# WKMiniFlyG4.net
KiCad netlist of a schematic drawn in EasyEDA Pro
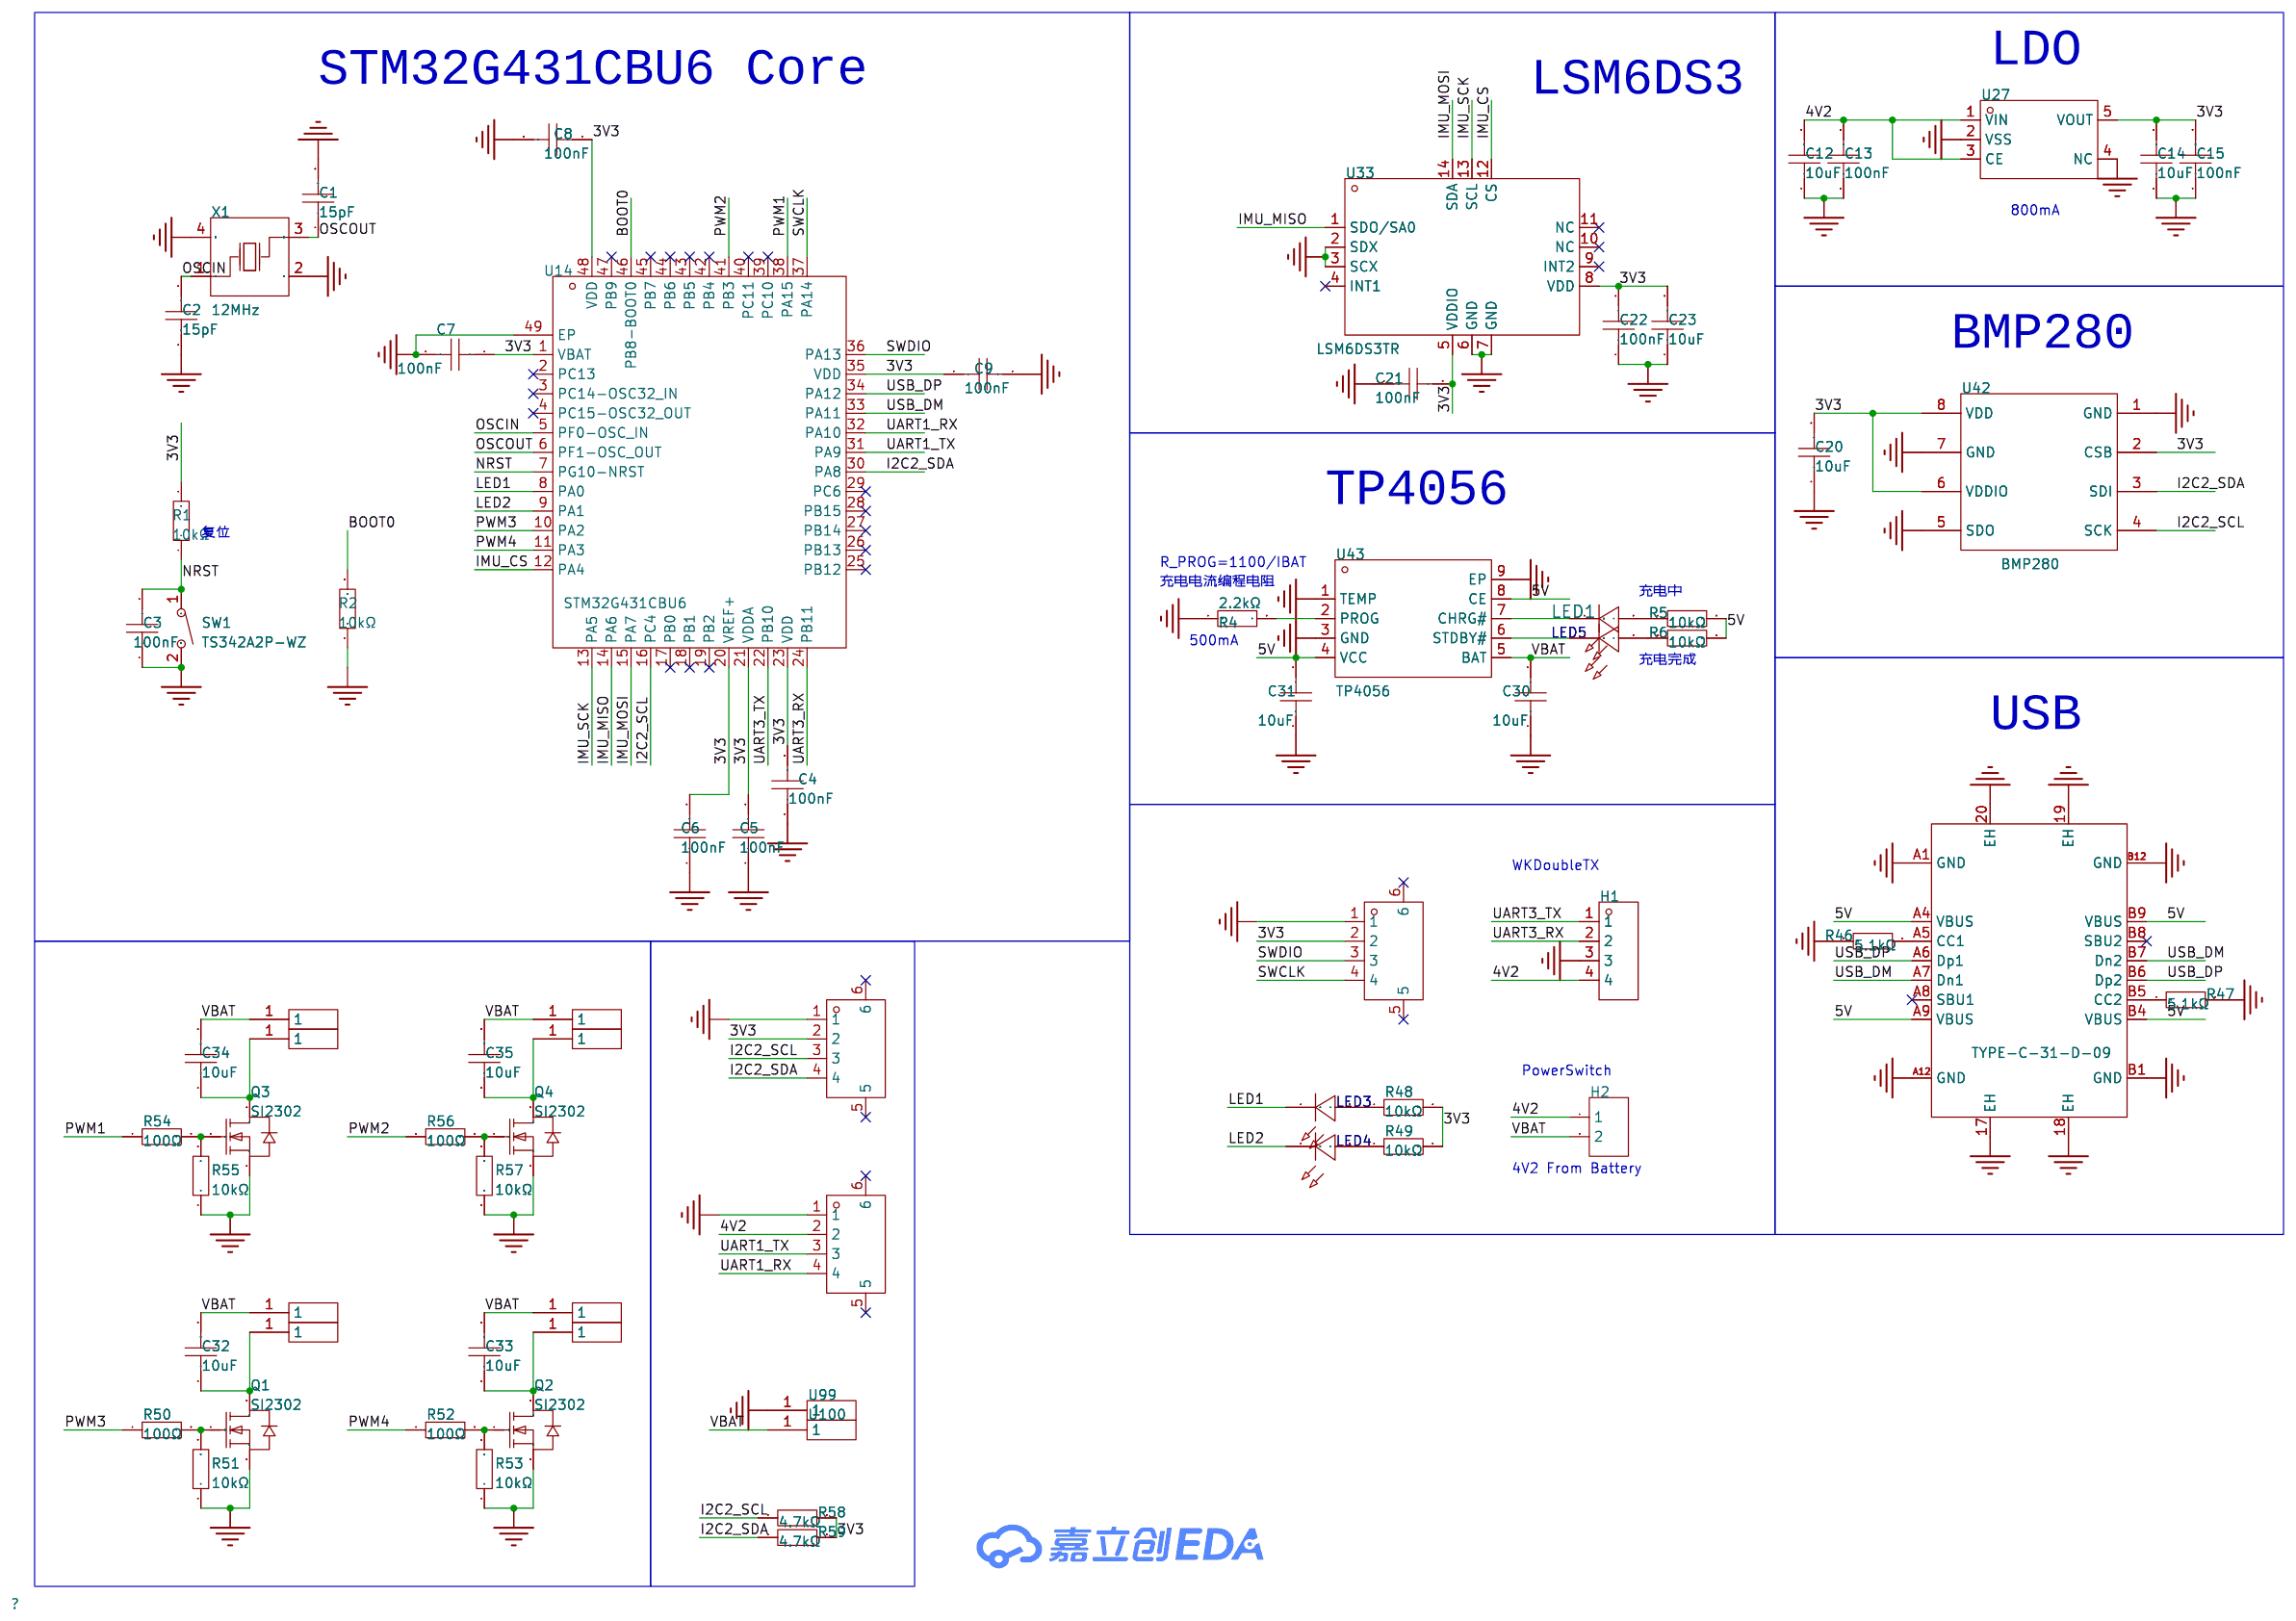
[diagram p0: schematic sheet]

(export (version "E")
  (design (tool "Eeschema 10.0.6"))
  (components
    (comp (ref "C1")
      (value "15pF")
      (footprint "easyedapro:C0603")
      (fields
        (field (name "Manufacturer Part") "CL10C150JB8NNNC")
        (field (name "Manufacturer") "SAMSUNG(三星)")
      )
      (libsource (lib "easyedapro") (part "CapAcitance"))
    )
    (comp (ref "C2")
      (value "15pF")
      (footprint "easyedapro:C0603")
      (fields
        (field (name "Manufacturer Part") "CL10C150JB8NNNC")
        (field (name "Manufacturer") "SAMSUNG(三星)")
      )
      (libsource (lib "easyedapro") (part "CapAcitance"))
    )
    (comp (ref "C3")
      (value "100nF")
      (footprint "easyedapro:C0603")
      (fields
        (field (name "Manufacturer Part") "CC0603KRX7R9BB104")
        (field (name "Manufacturer") "YAGEO(国巨)")
      )
      (libsource (lib "easyedapro") (part "CapAcitance"))
    )
    (comp (ref "C4")
      (value "100nF")
      (footprint "easyedapro:C0603")
      (fields
        (field (name "Manufacturer Part") "CC0603KRX7R9BB104")
        (field (name "Manufacturer") "YAGEO(国巨)")
      )
      (libsource (lib "easyedapro") (part "CapAcitance"))
    )
    (comp (ref "C5")
      (value "100nF")
      (footprint "easyedapro:C0603")
      (fields
        (field (name "Manufacturer Part") "CC0603KRX7R9BB104")
        (field (name "Manufacturer") "YAGEO(国巨)")
      )
      (libsource (lib "easyedapro") (part "CapAcitance"))
    )
    (comp (ref "C6")
      (value "100nF")
      (footprint "easyedapro:C0603")
      (fields
        (field (name "Manufacturer Part") "CC0603KRX7R9BB104")
        (field (name "Manufacturer") "YAGEO(国巨)")
      )
      (libsource (lib "easyedapro") (part "CapAcitance"))
    )
    (comp (ref "C7")
      (value "100nF")
      (footprint "easyedapro:C0603")
      (fields
        (field (name "Manufacturer Part") "CC0603KRX7R9BB104")
        (field (name "Manufacturer") "YAGEO(国巨)")
      )
      (libsource (lib "easyedapro") (part "CapAcitance"))
    )
    (comp (ref "C8")
      (value "100nF")
      (footprint "easyedapro:C0603")
      (fields
        (field (name "Manufacturer Part") "CC0603KRX7R9BB104")
        (field (name "Manufacturer") "YAGEO(国巨)")
      )
      (libsource (lib "easyedapro") (part "CapAcitance"))
    )
    (comp (ref "C9")
      (value "100nF")
      (footprint "easyedapro:C0603")
      (fields
        (field (name "Manufacturer Part") "CC0603KRX7R9BB104")
        (field (name "Manufacturer") "YAGEO(国巨)")
      )
      (libsource (lib "easyedapro") (part "CapAcitance"))
    )
    (comp (ref "C12")
      (value "10uF")
      (footprint "easyedapro:C0603")
      (fields
        (field (name "Manufacturer Part") "CL10A106KP8NNNC")
        (field (name "Manufacturer") "SAMSUNG(三星)")
      )
      (libsource (lib "easyedapro") (part "CapAcitance"))
    )
    (comp (ref "C13")
      (value "100nF")
      (footprint "easyedapro:C0603")
      (fields
        (field (name "Manufacturer Part") "CC0603KRX7R9BB104")
        (field (name "Manufacturer") "YAGEO(国巨)")
      )
      (libsource (lib "easyedapro") (part "CapAcitance"))
    )
    (comp (ref "C14")
      (value "10uF")
      (footprint "easyedapro:C0603")
      (fields
        (field (name "Manufacturer Part") "CL10A106KP8NNNC")
        (field (name "Manufacturer") "SAMSUNG(三星)")
      )
      (libsource (lib "easyedapro") (part "CapAcitance"))
    )
    (comp (ref "C15")
      (value "100nF")
      (footprint "easyedapro:C0603")
      (fields
        (field (name "Manufacturer Part") "CC0603KRX7R9BB104")
        (field (name "Manufacturer") "YAGEO(国巨)")
      )
      (libsource (lib "easyedapro") (part "CapAcitance"))
    )
    (comp (ref "C20")
      (value "10uF")
      (footprint "easyedapro:C0603")
      (fields
        (field (name "Manufacturer Part") "CL10A106KP8NNNC")
        (field (name "Manufacturer") "SAMSUNG(三星)")
      )
      (libsource (lib "easyedapro") (part "CapAcitance"))
    )
    (comp (ref "C21")
      (value "100nF")
      (footprint "easyedapro:C0603")
      (fields
        (field (name "Manufacturer Part") "CC0603KRX7R9BB104")
        (field (name "Manufacturer") "YAGEO(国巨)")
      )
      (libsource (lib "easyedapro") (part "CapAcitance"))
    )
    (comp (ref "C22")
      (value "100nF")
      (footprint "easyedapro:C0603")
      (fields
        (field (name "Manufacturer Part") "CC0603KRX7R9BB104")
        (field (name "Manufacturer") "YAGEO(国巨)")
      )
      (libsource (lib "easyedapro") (part "CapAcitance"))
    )
    (comp (ref "C23")
      (value "10uF")
      (footprint "easyedapro:C0603")
      (fields
        (field (name "Manufacturer Part") "CL10A106KP8NNNC")
        (field (name "Manufacturer") "SAMSUNG(三星)")
      )
      (libsource (lib "easyedapro") (part "CapAcitance"))
    )
    (comp (ref "C30")
      (value "10uF")
      (footprint "easyedapro:C0603")
      (fields
        (field (name "Manufacturer Part") "CL10A106KP8NNNC")
        (field (name "Manufacturer") "SAMSUNG(三星)")
      )
      (libsource (lib "easyedapro") (part "CapAcitance"))
    )
    (comp (ref "C31")
      (value "10uF")
      (footprint "easyedapro:C0603")
      (fields
        (field (name "Manufacturer Part") "CL10A106KP8NNNC")
        (field (name "Manufacturer") "SAMSUNG(三星)")
      )
      (libsource (lib "easyedapro") (part "CapAcitance"))
    )
    (comp (ref "C32")
      (value "10uF")
      (footprint "easyedapro:C0603")
      (fields
        (field (name "Manufacturer Part") "CL10A106KP8NNNC")
        (field (name "Manufacturer") "SAMSUNG(三星)")
      )
      (libsource (lib "easyedapro") (part "CapAcitance"))
    )
    (comp (ref "C33")
      (value "10uF")
      (footprint "easyedapro:C0603")
      (fields
        (field (name "Manufacturer Part") "CL10A106KP8NNNC")
        (field (name "Manufacturer") "SAMSUNG(三星)")
      )
      (libsource (lib "easyedapro") (part "CapAcitance"))
    )
    (comp (ref "C34")
      (value "10uF")
      (footprint "easyedapro:C0603")
      (fields
        (field (name "Manufacturer Part") "CL10A106KP8NNNC")
        (field (name "Manufacturer") "SAMSUNG(三星)")
      )
      (libsource (lib "easyedapro") (part "CapAcitance"))
    )
    (comp (ref "C35")
      (value "10uF")
      (footprint "easyedapro:C0603")
      (fields
        (field (name "Manufacturer Part") "CL10A106KP8NNNC")
        (field (name "Manufacturer") "SAMSUNG(三星)")
      )
      (libsource (lib "easyedapro") (part "CapAcitance"))
    )
    (comp (ref "H1")
      (value "~")
      (footprint "easyedapro:HDR-TH_4P-P2.54-V-M")
      (libsource (lib "easyedapro") (part "PZ254V-11-04P"))
    )
    (comp (ref "H2")
      (value "~")
      (footprint "easyedapro:HDR-TH_2P-P2.54-V-F")
      (libsource (lib "easyedapro") (part "Header-Female-2.54_1x2"))
    )
    (comp (ref "LED1")
      (value "~")
      (footprint "easyedapro:LED_0603")
      (libsource (lib "easyedapro") (part "LED_R"))
    )
    (comp (ref "LED3")
      (value "~")
      (footprint "easyedapro:LED_0603")
      (libsource (lib "easyedapro") (part "LED_G"))
    )
    (comp (ref "LED4")
      (value "~")
      (footprint "easyedapro:LED_0603")
      (libsource (lib "easyedapro") (part "LED_G"))
    )
    (comp (ref "LED5")
      (value "~")
      (footprint "easyedapro:LED_0603")
      (libsource (lib "easyedapro") (part "LED_G"))
    )
    (comp (ref "Q1")
      (value "SI2302")
      (footprint "easyedapro:SOT-23-3_L2.9-W1.3-P1.90-LS2.4-BR")
      (fields (field (name "Manufacturer") "YONGYUTAI(永裕泰)"))
      (libsource (lib "easyedapro") (part "SI2302_C2891732"))
    )
    (comp (ref "Q2")
      (value "SI2302")
      (footprint "easyedapro:SOT-23-3_L2.9-W1.3-P1.90-LS2.4-BR")
      (fields (field (name "Manufacturer") "YONGYUTAI(永裕泰)"))
      (libsource (lib "easyedapro") (part "SI2302_C2891732"))
    )
    (comp (ref "Q3")
      (value "SI2302")
      (footprint "easyedapro:SOT-23-3_L2.9-W1.3-P1.90-LS2.4-BR")
      (fields (field (name "Manufacturer") "YONGYUTAI(永裕泰)"))
      (libsource (lib "easyedapro") (part "SI2302_C2891732"))
    )
    (comp (ref "Q4")
      (value "SI2302")
      (footprint "easyedapro:SOT-23-3_L2.9-W1.3-P1.90-LS2.4-BR")
      (fields (field (name "Manufacturer") "YONGYUTAI(永裕泰)"))
      (libsource (lib "easyedapro") (part "SI2302_C2891732"))
    )
    (comp (ref "R1")
      (value "10kΩ")
      (footprint "easyedapro:R0603")
      (fields
        (field (name "Manufacturer Part") "0603WAF1002T5E")
        (field (name "Manufacturer") "UNI-ROYAL(厚声)")
      )
      (libsource (lib "easyedapro") (part "电阻"))
    )
    (comp (ref "R2")
      (value "10kΩ")
      (footprint "easyedapro:R0603")
      (fields
        (field (name "Manufacturer Part") "0603WAF1002T5E")
        (field (name "Manufacturer") "UNI-ROYAL(厚声)")
      )
      (libsource (lib "easyedapro") (part "电阻"))
    )
    (comp (ref "R4")
      (value "2.2kΩ")
      (footprint "easyedapro:R0603")
      (fields
        (field (name "Manufacturer Part") "0603WAF2201T5E")
        (field (name "Manufacturer") "UNI-ROYAL(厚声)")
      )
      (libsource (lib "easyedapro") (part "电阻"))
    )
    (comp (ref "R5")
      (value "10kΩ")
      (footprint "easyedapro:R0603")
      (fields
        (field (name "Manufacturer Part") "0603WAF1002T5E")
        (field (name "Manufacturer") "UNI-ROYAL(厚声)")
      )
      (libsource (lib "easyedapro") (part "电阻"))
    )
    (comp (ref "R6")
      (value "10kΩ")
      (footprint "easyedapro:R0603")
      (fields
        (field (name "Manufacturer Part") "0603WAF1002T5E")
        (field (name "Manufacturer") "UNI-ROYAL(厚声)")
      )
      (libsource (lib "easyedapro") (part "电阻"))
    )
    (comp (ref "R46")
      (value "5.1kΩ")
      (footprint "easyedapro:R0603")
      (fields
        (field (name "Manufacturer Part") "0603WAF5101T5E")
        (field (name "Manufacturer") "UNI-ROYAL(厚声)")
      )
      (libsource (lib "easyedapro") (part "电阻"))
    )
    (comp (ref "R47")
      (value "5.1kΩ")
      (footprint "easyedapro:R0603")
      (fields
        (field (name "Manufacturer Part") "0603WAF5101T5E")
        (field (name "Manufacturer") "UNI-ROYAL(厚声)")
      )
      (libsource (lib "easyedapro") (part "电阻"))
    )
    (comp (ref "R48")
      (value "10kΩ")
      (footprint "easyedapro:R0603")
      (fields
        (field (name "Manufacturer Part") "0603WAF1002T5E")
        (field (name "Manufacturer") "UNI-ROYAL(厚声)")
      )
      (libsource (lib "easyedapro") (part "电阻"))
    )
    (comp (ref "R49")
      (value "10kΩ")
      (footprint "easyedapro:R0603")
      (fields
        (field (name "Manufacturer Part") "0603WAF1002T5E")
        (field (name "Manufacturer") "UNI-ROYAL(厚声)")
      )
      (libsource (lib "easyedapro") (part "电阻"))
    )
    (comp (ref "R50")
      (value "100Ω")
      (footprint "easyedapro:R0603")
      (fields
        (field (name "Manufacturer Part") "0603WAF1000T5E")
        (field (name "Manufacturer") "UNI-ROYAL(厚声)")
      )
      (libsource (lib "easyedapro") (part "电阻"))
    )
    (comp (ref "R51")
      (value "10kΩ")
      (footprint "easyedapro:R0603")
      (fields
        (field (name "Manufacturer Part") "0603WAF1002T5E")
        (field (name "Manufacturer") "UNI-ROYAL(厚声)")
      )
      (libsource (lib "easyedapro") (part "电阻"))
    )
    (comp (ref "R52")
      (value "100Ω")
      (footprint "easyedapro:R0603")
      (fields
        (field (name "Manufacturer Part") "0603WAF1000T5E")
        (field (name "Manufacturer") "UNI-ROYAL(厚声)")
      )
      (libsource (lib "easyedapro") (part "电阻"))
    )
    (comp (ref "R53")
      (value "10kΩ")
      (footprint "easyedapro:R0603")
      (fields
        (field (name "Manufacturer Part") "0603WAF1002T5E")
        (field (name "Manufacturer") "UNI-ROYAL(厚声)")
      )
      (libsource (lib "easyedapro") (part "电阻"))
    )
    (comp (ref "R54")
      (value "100Ω")
      (footprint "easyedapro:R0603")
      (fields
        (field (name "Manufacturer Part") "0603WAF1000T5E")
        (field (name "Manufacturer") "UNI-ROYAL(厚声)")
      )
      (libsource (lib "easyedapro") (part "电阻"))
    )
    (comp (ref "R55")
      (value "10kΩ")
      (footprint "easyedapro:R0603")
      (fields
        (field (name "Manufacturer Part") "0603WAF1002T5E")
        (field (name "Manufacturer") "UNI-ROYAL(厚声)")
      )
      (libsource (lib "easyedapro") (part "电阻"))
    )
    (comp (ref "R56")
      (value "100Ω")
      (footprint "easyedapro:R0603")
      (fields
        (field (name "Manufacturer Part") "0603WAF1000T5E")
        (field (name "Manufacturer") "UNI-ROYAL(厚声)")
      )
      (libsource (lib "easyedapro") (part "电阻"))
    )
    (comp (ref "R57")
      (value "10kΩ")
      (footprint "easyedapro:R0603")
      (fields
        (field (name "Manufacturer Part") "0603WAF1002T5E")
        (field (name "Manufacturer") "UNI-ROYAL(厚声)")
      )
      (libsource (lib "easyedapro") (part "电阻"))
    )
    (comp (ref "R58")
      (value "4.7kΩ")
      (footprint "easyedapro:R0603")
      (fields
        (field (name "Manufacturer Part") "0603WAF4701T5E")
        (field (name "Manufacturer") "UNI-ROYAL(厚声)")
      )
      (libsource (lib "easyedapro") (part "电阻"))
    )
    (comp (ref "R59")
      (value "4.7kΩ")
      (footprint "easyedapro:R0603")
      (fields
        (field (name "Manufacturer Part") "0603WAF4701T5E")
        (field (name "Manufacturer") "UNI-ROYAL(厚声)")
      )
      (libsource (lib "easyedapro") (part "电阻"))
    )
    (comp (ref "SW1")
      (value "TS342A2P-WZ")
      (footprint "easyedapro:SW-SMD_L4.0-W2.9-LS5.0")
      (fields (field (name "Manufacturer") "SHOU HAN(首韩)"))
      (libsource (lib "easyedapro") (part "TS342A2P-WZ"))
    )
    (comp (ref "U14")
      (value "STM32G431CBU6")
      (footprint "easyedapro:UFQFPN-48_L7.0-W7.0-P0.50-BL-EP")
      (description "CPU内核:ARM-M系列;程序存储容量:128KB;RAM总容量:32KB;GPIO端口数量:42;工作电压范围:1.71V~3.6V;CPU最大主频:170MHz;程序存储器类型:FLASH;")
      (fields (field (name "Manufacturer") "ST(意法半导体)"))
      (libsource (lib "easyedapro") (part "STM32G431CBU6"))
    )
    (comp (ref "U27")
      (value "ME6217C33M5G")
      (footprint "easyedapro:SOT-23-5_L3.0-W1.7-P0.95-LS2.8-BR")
      (description "输出类型:固定;输出极性:正;最大输入电压:7V;输出电压:3.3V;输出电流:800mA;电源纹波抑制比(PSRR):65dB@(1kHz);")
      (fields (field (name "Manufacturer") "MICRONE(南京微盟)"))
      (libsource (lib "easyedapro") (part "ME6217C33M5G"))
    )
    (comp (ref "U33")
      (value "LSM6DS3TR")
      (footprint "easyedapro:LGA-14_L3.0-W2.5-P0.50-TL")
      (description "传感器类型:加速度计陀螺仪;")
      (fields (field (name "Manufacturer") "ST(意法半导体)"))
      (libsource (lib "easyedapro") (part "LSM6DS3TR"))
    )
    (comp (ref "U39")
      (value "ZX-SH1.0-4PWT")
      (footprint "easyedapro:CONN-SMD_4P-P1.00_MEGASTAR_ZX-SH1.0-4PWT")
      (description "插针结构:1x4P;间距:1mm;安装方式:卧贴;参考系列:SH;总PIN数:4P;排数:1;每排PIN数:4;行距:-;额定电流:-;触头材质:黄铜;触头镀层:锡;工作温度范围:-;")
      (fields (field (name "Manufacturer") "Megastar(兆星)"))
      (libsource (lib "easyedapro") (part "ZX-SH1.0-4PWT"))
    )
    (comp (ref "U41")
      (value "ZX-SH1.0-4PWT")
      (footprint "easyedapro:CONN-SMD_4P-P1.00_MEGASTAR_ZX-SH1.0-4PWT")
      (description "插针结构:1x4P;间距:1mm;安装方式:卧贴;参考系列:SH;总PIN数:4P;排数:1;每排PIN数:4;行距:-;额定电流:-;触头材质:黄铜;触头镀层:锡;工作温度范围:-;")
      (fields (field (name "Manufacturer") "Megastar(兆星)"))
      (libsource (lib "easyedapro") (part "ZX-SH1.0-4PWT"))
    )
    (comp (ref "U42")
      (value "BMP280")
      (footprint "easyedapro:LGA-8_L2.5-W2.0-P0.65_AMP6127")
      (description "Bosch气压传感器新品，可测量大气压力，带高精度温度测量，可校准精确计算海拔高度。I2C或SPI接口，宽量程（300-1100hpa），精度高")
      (fields (field (name "Manufacturer") "Bosch(博世)"))
      (libsource (lib "easyedapro") (part "BMP280"))
    )
    (comp (ref "U43")
      (value "TP4056")
      (footprint "easyedapro:ESOP-8_L4.9-W3.9-P1.27-LS6.0-BL-EP")
      (description "工作电压:4V~6V;最大充电电流:1A;电池类型:锂离子/聚合物;电池节数:1;")
      (fields (field (name "Manufacturer") "TPOWER(天源)"))
      (libsource (lib "easyedapro") (part "TP4056_C382139"))
    )
    (comp (ref "U89")
      (value "TYPE-C-31-D-09")
      (footprint "easyedapro:USB-C-TH_TYPE-C-31-D-09")
      (description "连接器类型:Type-C;公母:母;触点数量:16P;端口数量:1;触头材质:磷青铜;触头镀层:金;工作温度范围:-25°C~+85°C;焊接温度(最大值):255°C;")
      (fields (field (name "Manufacturer") "韩国韩荣"))
      (libsource (lib "easyedapro") (part "TYPE-C-31-D-09_C7463258"))
    )
    (comp (ref "U90")
      (value "~")
      (footprint "easyedapro:1pin焊接引出")
      (libsource (lib "easyedapro") (part "1pin焊接引出"))
    )
    (comp (ref "U91")
      (value "~")
      (footprint "easyedapro:1pin焊接引出")
      (libsource (lib "easyedapro") (part "1pin焊接引出"))
    )
    (comp (ref "U92")
      (value "~")
      (footprint "easyedapro:1pin焊接引出")
      (libsource (lib "easyedapro") (part "1pin焊接引出"))
    )
    (comp (ref "U93")
      (value "~")
      (footprint "easyedapro:1pin焊接引出")
      (libsource (lib "easyedapro") (part "1pin焊接引出"))
    )
    (comp (ref "U94")
      (value "~")
      (footprint "easyedapro:1pin焊接引出")
      (libsource (lib "easyedapro") (part "1pin焊接引出"))
    )
    (comp (ref "U95")
      (value "~")
      (footprint "easyedapro:1pin焊接引出")
      (libsource (lib "easyedapro") (part "1pin焊接引出"))
    )
    (comp (ref "U96")
      (value "~")
      (footprint "easyedapro:1pin焊接引出")
      (libsource (lib "easyedapro") (part "1pin焊接引出"))
    )
    (comp (ref "U97")
      (value "~")
      (footprint "easyedapro:1pin焊接引出")
      (libsource (lib "easyedapro") (part "1pin焊接引出"))
    )
    (comp (ref "U98")
      (value "ZX-SH1.0-4PWT")
      (footprint "easyedapro:CONN-SMD_4P-P1.00_MEGASTAR_ZX-SH1.0-4PWT")
      (description "插针结构:1x4P;间距:1mm;安装方式:卧贴;参考系列:SH;总PIN数:4P;排数:1;每排PIN数:4;行距:-;额定电流:-;触头材质:黄铜;触头镀层:锡;工作温度范围:-;")
      (fields (field (name "Manufacturer") "Megastar(兆星)"))
      (libsource (lib "easyedapro") (part "ZX-SH1.0-4PWT"))
    )
    (comp (ref "U99")
      (value "~")
      (footprint "easyedapro:1pin焊接引出")
      (libsource (lib "easyedapro") (part "1pin焊接引出"))
    )
    (comp (ref "U100")
      (value "~")
      (footprint "easyedapro:1pin焊接引出")
      (libsource (lib "easyedapro") (part "1pin焊接引出"))
    )
    (comp (ref "X1")
      (value "12MHz")
      (footprint "easyedapro:OSC-SMD_4P-L3.2-W2.5-BL")
      (description "晶振类型:贴片晶振;频率:12MHz;常温频差:±10ppm;外接负载电容:20pF;频率稳定度(全温):±30ppm;")
      (fields (field (name "Manufacturer Part") "X322512MSB4SI") (field (name "Manufacturer") "YXC(扬兴晶振)"))
      (libsource (lib "easyedapro") (part "X322512MSB4SI"))
    )
  )
  (nets
    (net (code "1") (name "/3V3") (class "Default")
      (node (ref "C14") (pin "2") (pinfunction "2_2") (pintype "input"))
      (node (ref "C15") (pin "2") (pinfunction "2_2") (pintype "input"))
      (node (ref "C20") (pin "2") (pinfunction "2_2") (pintype "input"))
      (node (ref "C21") (pin "2") (pinfunction "2_2") (pintype "input"))
      (node (ref "C22") (pin "2") (pinfunction "2_2") (pintype "input"))
      (node (ref "C23") (pin "2") (pinfunction "2_2") (pintype "input"))
      (node (ref "C4") (pin "2") (pinfunction "2_2") (pintype "input"))
      (node (ref "C5") (pin "2") (pinfunction "2_2") (pintype "input"))
      (node (ref "C6") (pin "2") (pinfunction "2_2") (pintype "input"))
      (node (ref "C7") (pin "1") (pinfunction "1_1") (pintype "input"))
      (node (ref "C8") (pin "1") (pinfunction "1_1") (pintype "input"))
      (node (ref "C9") (pin "1") (pinfunction "1_1") (pintype "input"))
      (node (ref "R1") (pin "2") (pinfunction "2_2") (pintype "input"))
      (node (ref "R48") (pin "2") (pinfunction "2_2") (pintype "input"))
      (node (ref "R49") (pin "2") (pinfunction "2_2") (pintype "input"))
      (node (ref "R58") (pin "2") (pinfunction "2_2") (pintype "input"))
      (node (ref "R59") (pin "2") (pinfunction "2_2") (pintype "input"))
      (node (ref "U14") (pin "1") (pinfunction "VBAT_1") (pintype "unspecified"))
      (node (ref "U14") (pin "20") (pinfunction "VREF+_20") (pintype "unspecified"))
      (node (ref "U14") (pin "21") (pinfunction "VDDA_21") (pintype "unspecified"))
      (node (ref "U14") (pin "23") (pinfunction "VDD_23") (pintype "unspecified"))
      (node (ref "U14") (pin "35") (pinfunction "VDD_35") (pintype "unspecified"))
      (node (ref "U14") (pin "48") (pinfunction "VDD_48") (pintype "unspecified"))
      (node (ref "U27") (pin "5") (pinfunction "VOUT_5") (pintype "input"))
      (node (ref "U33") (pin "5") (pinfunction "VDDIO_5") (pintype "unspecified"))
      (node (ref "U33") (pin "8") (pinfunction "VDD_8") (pintype "unspecified"))
      (node (ref "U39") (pin "2") (pinfunction "2_2") (pintype "unspecified"))
      (node (ref "U41") (pin "2") (pinfunction "2_2") (pintype "unspecified"))
      (node (ref "U42") (pin "2") (pinfunction "CSB_2") (pintype "unspecified"))
      (node (ref "U42") (pin "6") (pinfunction "VDDIO_6") (pintype "unspecified"))
      (node (ref "U42") (pin "8") (pinfunction "VDD_8") (pintype "unspecified"))
    )
    (net (code "2") (name "/4V2") (class "Default")
      (node (ref "C12") (pin "2") (pinfunction "2_2") (pintype "input"))
      (node (ref "C13") (pin "2") (pinfunction "2_2") (pintype "input"))
      (node (ref "H1") (pin "4") (pinfunction "4_4") (pintype "unspecified"))
      (node (ref "H2") (pin "1") (pinfunction "1_1") (pintype "input"))
      (node (ref "U27") (pin "1") (pinfunction "VIN_1") (pintype "input"))
      (node (ref "U27") (pin "3") (pinfunction "CE_3") (pintype "input"))
      (node (ref "U98") (pin "2") (pinfunction "2_2") (pintype "unspecified"))
    )
    (net (code "3") (name "/5V") (class "Default")
      (node (ref "C31") (pin "2") (pinfunction "2_2") (pintype "input"))
      (node (ref "R5") (pin "2") (pinfunction "2_2") (pintype "input"))
      (node (ref "R6") (pin "2") (pinfunction "2_2") (pintype "input"))
      (node (ref "U43") (pin "4") (pinfunction "VCC_4") (pintype "unspecified"))
      (node (ref "U43") (pin "8") (pinfunction "CE_8") (pintype "unspecified"))
      (node (ref "U89") (pin "A4") (pinfunction "VBUS_A4") (pintype "unspecified"))
      (node (ref "U89") (pin "A9") (pinfunction "VBUS_A9") (pintype "unspecified"))
      (node (ref "U89") (pin "B4") (pinfunction "VBUS_B4") (pintype "unspecified"))
      (node (ref "U89") (pin "B9") (pinfunction "VBUS_B9") (pintype "unspecified"))
    )
    (net (code "4") (name "/BOOT0") (class "Default")
      (node (ref "R2") (pin "2") (pinfunction "2_2") (pintype "input"))
      (node (ref "U14") (pin "46") (pinfunction "PB8-BOOT0_46") (pintype "unspecified"))
    )
    (net (code "5") (name "/I2C2_SCL") (class "Default")
      (node (ref "R58") (pin "1") (pinfunction "1_1") (pintype "input"))
      (node (ref "U14") (pin "16") (pinfunction "PC4_16") (pintype "unspecified"))
      (node (ref "U39") (pin "3") (pinfunction "3_3") (pintype "unspecified"))
      (node (ref "U42") (pin "4") (pinfunction "SCK_4") (pintype "unspecified"))
    )
    (net (code "6") (name "/I2C2_SDA") (class "Default")
      (node (ref "R59") (pin "1") (pinfunction "1_1") (pintype "input"))
      (node (ref "U14") (pin "30") (pinfunction "PA8_30") (pintype "unspecified"))
      (node (ref "U39") (pin "4") (pinfunction "4_4") (pintype "unspecified"))
      (node (ref "U42") (pin "3") (pinfunction "SDI_3") (pintype "unspecified"))
    )
    (net (code "7") (name "/IMU_CS") (class "Default")
      (node (ref "U14") (pin "12") (pinfunction "PA4_12") (pintype "unspecified"))
      (node (ref "U33") (pin "12") (pinfunction "CS_12") (pintype "unspecified"))
    )
    (net (code "8") (name "/IMU_MISO") (class "Default")
      (node (ref "U14") (pin "14") (pinfunction "PA6_14") (pintype "unspecified"))
      (node (ref "U33") (pin "1") (pinfunction "SDO/SA0_1") (pintype "unspecified"))
    )
    (net (code "9") (name "/IMU_MOSI") (class "Default")
      (node (ref "U14") (pin "15") (pinfunction "PA7_15") (pintype "unspecified"))
      (node (ref "U33") (pin "14") (pinfunction "SDA_14") (pintype "unspecified"))
    )
    (net (code "10") (name "/IMU_SCK") (class "Default")
      (node (ref "U14") (pin "13") (pinfunction "PA5_13") (pintype "unspecified"))
      (node (ref "U33") (pin "13") (pinfunction "SCL_13") (pintype "unspecified"))
    )
    (net (code "11") (name "/LED1") (class "Default")
      (node (ref "LED3") (pin "1") (pinfunction "C_1") (pintype "input"))
      (node (ref "U14") (pin "8") (pinfunction "PA0_8") (pintype "unspecified"))
    )
    (net (code "12") (name "/LED2") (class "Default")
      (node (ref "LED4") (pin "1") (pinfunction "C_1") (pintype "input"))
      (node (ref "U14") (pin "9") (pinfunction "PA1_9") (pintype "unspecified"))
    )
    (net (code "13") (name "/NRST") (class "Default")
      (node (ref "C3") (pin "2") (pinfunction "2_2") (pintype "input"))
      (node (ref "R1") (pin "1") (pinfunction "1_1") (pintype "input"))
      (node (ref "SW1") (pin "1") (pinfunction "1_1") (pintype "unspecified"))
      (node (ref "U14") (pin "7") (pinfunction "PG10-NRST_7") (pintype "unspecified"))
    )
    (net (code "14") (name "/OSCIN") (class "Default")
      (node (ref "C2") (pin "2") (pinfunction "2_2") (pintype "input"))
      (node (ref "U14") (pin "5") (pinfunction "PF0-OSC_IN_5") (pintype "unspecified"))
      (node (ref "X1") (pin "1") (pinfunction "OSC1_1") (pintype "input"))
    )
    (net (code "15") (name "/OSCOUT") (class "Default")
      (node (ref "C1") (pin "1") (pinfunction "1_1") (pintype "input"))
      (node (ref "U14") (pin "6") (pinfunction "PF1-OSC_OUT_6") (pintype "unspecified"))
      (node (ref "X1") (pin "3") (pinfunction "OSC2_3") (pintype "input"))
    )
    (net (code "16") (name "/PWM1") (class "Default")
      (node (ref "R54") (pin "1") (pinfunction "1_1") (pintype "input"))
      (node (ref "U14") (pin "38") (pinfunction "PA15_38") (pintype "unspecified"))
    )
    (net (code "17") (name "/PWM2") (class "Default")
      (node (ref "R56") (pin "1") (pinfunction "1_1") (pintype "input"))
      (node (ref "U14") (pin "41") (pinfunction "PB3_41") (pintype "unspecified"))
    )
    (net (code "18") (name "/PWM3") (class "Default")
      (node (ref "R50") (pin "1") (pinfunction "1_1") (pintype "input"))
      (node (ref "U14") (pin "10") (pinfunction "PA2_10") (pintype "unspecified"))
    )
    (net (code "19") (name "/PWM4") (class "Default")
      (node (ref "R52") (pin "1") (pinfunction "1_1") (pintype "input"))
      (node (ref "U14") (pin "11") (pinfunction "PA3_11") (pintype "unspecified"))
    )
    (net (code "20") (name "/SWCLK") (class "Default")
      (node (ref "U14") (pin "37") (pinfunction "PA14_37") (pintype "unspecified"))
      (node (ref "U41") (pin "4") (pinfunction "4_4") (pintype "unspecified"))
    )
    (net (code "21") (name "/SWDIO") (class "Default")
      (node (ref "U14") (pin "36") (pinfunction "PA13_36") (pintype "unspecified"))
      (node (ref "U41") (pin "3") (pinfunction "3_3") (pintype "unspecified"))
    )
    (net (code "22") (name "/UART1_RX") (class "Default")
      (node (ref "U14") (pin "32") (pinfunction "PA10_32") (pintype "unspecified"))
      (node (ref "U98") (pin "4") (pinfunction "4_4") (pintype "unspecified"))
    )
    (net (code "23") (name "/UART1_TX") (class "Default")
      (node (ref "U14") (pin "31") (pinfunction "PA9_31") (pintype "unspecified"))
      (node (ref "U98") (pin "3") (pinfunction "3_3") (pintype "unspecified"))
    )
    (net (code "24") (name "/UART3_RX") (class "Default")
      (node (ref "H1") (pin "2") (pinfunction "2_2") (pintype "unspecified"))
      (node (ref "U14") (pin "24") (pinfunction "PB11_24") (pintype "unspecified"))
    )
    (net (code "25") (name "/UART3_TX") (class "Default")
      (node (ref "H1") (pin "1") (pinfunction "1_1") (pintype "unspecified"))
      (node (ref "U14") (pin "22") (pinfunction "PB10_22") (pintype "unspecified"))
    )
    (net (code "26") (name "/USB_DM") (class "Default")
      (node (ref "U14") (pin "33") (pinfunction "PA11_33") (pintype "unspecified"))
      (node (ref "U89") (pin "A7") (pinfunction "Dn1_A7") (pintype "unspecified"))
      (node (ref "U89") (pin "B7") (pinfunction "Dn2_B7") (pintype "unspecified"))
    )
    (net (code "27") (name "/USB_DP") (class "Default")
      (node (ref "U14") (pin "34") (pinfunction "PA12_34") (pintype "unspecified"))
      (node (ref "U89") (pin "A6") (pinfunction "Dp1_A6") (pintype "unspecified"))
      (node (ref "U89") (pin "B6") (pinfunction "Dp2_B6") (pintype "unspecified"))
    )
    (net (code "28") (name "/VBAT") (class "Default")
      (node (ref "C30") (pin "2") (pinfunction "2_2") (pintype "input"))
      (node (ref "C32") (pin "2") (pinfunction "2_2") (pintype "input"))
      (node (ref "C33") (pin "2") (pinfunction "2_2") (pintype "input"))
      (node (ref "C34") (pin "2") (pinfunction "2_2") (pintype "input"))
      (node (ref "C35") (pin "2") (pinfunction "2_2") (pintype "input"))
      (node (ref "H2") (pin "2") (pinfunction "2_2") (pintype "input"))
      (node (ref "U100") (pin "1") (pinfunction "1_1") (pintype "input"))
      (node (ref "U43") (pin "5") (pinfunction "BAT_5") (pintype "unspecified"))
      (node (ref "U90") (pin "1") (pinfunction "1_1") (pintype "input"))
      (node (ref "U92") (pin "1") (pinfunction "1_1") (pintype "input"))
      (node (ref "U94") (pin "1") (pinfunction "1_1") (pintype "input"))
      (node (ref "U96") (pin "1") (pinfunction "1_1") (pintype "input"))
    )
    (net (code "29") (name "GND") (class "Default")
      (node (ref "C1") (pin "2") (pinfunction "2_2") (pintype "input"))
      (node (ref "C12") (pin "1") (pinfunction "1_1") (pintype "input"))
      (node (ref "C13") (pin "1") (pinfunction "1_1") (pintype "input"))
      (node (ref "C14") (pin "1") (pinfunction "1_1") (pintype "input"))
      (node (ref "C15") (pin "1") (pinfunction "1_1") (pintype "input"))
      (node (ref "C2") (pin "1") (pinfunction "1_1") (pintype "input"))
      (node (ref "C20") (pin "1") (pinfunction "1_1") (pintype "input"))
      (node (ref "C21") (pin "1") (pinfunction "1_1") (pintype "input"))
      (node (ref "C22") (pin "1") (pinfunction "1_1") (pintype "input"))
      (node (ref "C23") (pin "1") (pinfunction "1_1") (pintype "input"))
      (node (ref "C3") (pin "1") (pinfunction "1_1") (pintype "input"))
      (node (ref "C30") (pin "1") (pinfunction "1_1") (pintype "input"))
      (node (ref "C31") (pin "1") (pinfunction "1_1") (pintype "input"))
      (node (ref "C4") (pin "1") (pinfunction "1_1") (pintype "input"))
      (node (ref "C5") (pin "1") (pinfunction "1_1") (pintype "input"))
      (node (ref "C6") (pin "1") (pinfunction "1_1") (pintype "input"))
      (node (ref "C7") (pin "2") (pinfunction "2_2") (pintype "input"))
      (node (ref "C8") (pin "2") (pinfunction "2_2") (pintype "input"))
      (node (ref "C9") (pin "2") (pinfunction "2_2") (pintype "input"))
      (node (ref "H1") (pin "3") (pinfunction "3_3") (pintype "unspecified"))
      (node (ref "Q1") (pin "2") (pinfunction "S_2") (pintype "unspecified"))
      (node (ref "Q2") (pin "2") (pinfunction "S_2") (pintype "unspecified"))
      (node (ref "Q3") (pin "2") (pinfunction "S_2") (pintype "unspecified"))
      (node (ref "Q4") (pin "2") (pinfunction "S_2") (pintype "unspecified"))
      (node (ref "R2") (pin "1") (pinfunction "1_1") (pintype "input"))
      (node (ref "R4") (pin "1") (pinfunction "1_1") (pintype "input"))
      (node (ref "R46") (pin "1") (pinfunction "1_1") (pintype "input"))
      (node (ref "R47") (pin "2") (pinfunction "2_2") (pintype "input"))
      (node (ref "R51") (pin "1") (pinfunction "1_1") (pintype "input"))
      (node (ref "R53") (pin "1") (pinfunction "1_1") (pintype "input"))
      (node (ref "R55") (pin "1") (pinfunction "1_1") (pintype "input"))
      (node (ref "R57") (pin "1") (pinfunction "1_1") (pintype "input"))
      (node (ref "SW1") (pin "2") (pinfunction "2_2") (pintype "unspecified"))
      (node (ref "U14") (pin "49") (pinfunction "EP_49") (pintype "unspecified"))
      (node (ref "U27") (pin "2") (pinfunction "VSS_2") (pintype "input"))
      (node (ref "U27") (pin "4") (pinfunction "NC_4") (pintype "input"))
      (node (ref "U33") (pin "2") (pinfunction "SDX_2") (pintype "unspecified"))
      (node (ref "U33") (pin "3") (pinfunction "SCX_3") (pintype "unspecified"))
      (node (ref "U33") (pin "6") (pinfunction "GND_6") (pintype "unspecified"))
      (node (ref "U33") (pin "7") (pinfunction "GND_7") (pintype "unspecified"))
      (node (ref "U39") (pin "1") (pinfunction "1_1") (pintype "unspecified"))
      (node (ref "U41") (pin "1") (pinfunction "1_1") (pintype "unspecified"))
      (node (ref "U42") (pin "1") (pinfunction "GND_1") (pintype "unspecified"))
      (node (ref "U42") (pin "5") (pinfunction "SDO_5") (pintype "unspecified"))
      (node (ref "U42") (pin "7") (pinfunction "GND_7") (pintype "unspecified"))
      (node (ref "U43") (pin "1") (pinfunction "TEMP_1") (pintype "unspecified"))
      (node (ref "U43") (pin "3") (pinfunction "GND_3") (pintype "unspecified"))
      (node (ref "U43") (pin "9") (pinfunction "EP_9") (pintype "unspecified"))
      (node (ref "U89") (pin "17") (pinfunction "EH_17") (pintype "unspecified"))
      (node (ref "U89") (pin "18") (pinfunction "EH_18") (pintype "unspecified"))
      (node (ref "U89") (pin "19") (pinfunction "EH_19") (pintype "unspecified"))
      (node (ref "U89") (pin "20") (pinfunction "EH_20") (pintype "unspecified"))
      (node (ref "U89") (pin "A1") (pinfunction "GND_A1") (pintype "unspecified"))
      (node (ref "U89") (pin "A12") (pinfunction "GND_A12") (pintype "unspecified"))
      (node (ref "U89") (pin "B1") (pinfunction "GND_B1") (pintype "unspecified"))
      (node (ref "U89") (pin "B12") (pinfunction "GND_B12") (pintype "unspecified"))
      (node (ref "U98") (pin "1") (pinfunction "1_1") (pintype "unspecified"))
      (node (ref "U99") (pin "1") (pinfunction "1_1") (pintype "input"))
      (node (ref "X1") (pin "2") (pinfunction "GND_2") (pintype "input"))
      (node (ref "X1") (pin "4") (pinfunction "GND_4") (pintype "input"))
    )
    (net (code "30") (name "Net-(LED1-A)") (class "Default")
      (node (ref "LED1") (pin "2") (pinfunction "A_2") (pintype "input"))
      (node (ref "R5") (pin "1") (pinfunction "1_1") (pintype "input"))
    )
    (net (code "31") (name "Net-(LED1-C)") (class "Default")
      (node (ref "LED1") (pin "1") (pinfunction "C_1") (pintype "input"))
      (node (ref "U43") (pin "7") (pinfunction "CHRG#_7") (pintype "unspecified"))
    )
    (net (code "32") (name "Net-(LED3-A)") (class "Default")
      (node (ref "LED3") (pin "2") (pinfunction "A_2") (pintype "input"))
      (node (ref "R48") (pin "1") (pinfunction "1_1") (pintype "input"))
    )
    (net (code "33") (name "Net-(LED4-A)") (class "Default")
      (node (ref "LED4") (pin "2") (pinfunction "A_2") (pintype "input"))
      (node (ref "R49") (pin "1") (pinfunction "1_1") (pintype "input"))
    )
    (net (code "34") (name "Net-(LED5-A)") (class "Default")
      (node (ref "LED5") (pin "2") (pinfunction "A_2") (pintype "input"))
      (node (ref "R6") (pin "1") (pinfunction "1_1") (pintype "input"))
    )
    (net (code "35") (name "Net-(LED5-C)") (class "Default")
      (node (ref "LED5") (pin "1") (pinfunction "C_1") (pintype "input"))
      (node (ref "U43") (pin "6") (pinfunction "STDBY#_6") (pintype "unspecified"))
    )
    (net (code "36") (name "Net-(Q1-D)") (class "Default")
      (node (ref "C32") (pin "1") (pinfunction "1_1") (pintype "input"))
      (node (ref "Q1") (pin "3") (pinfunction "D_3") (pintype "unspecified"))
      (node (ref "U95") (pin "1") (pinfunction "1_1") (pintype "input"))
    )
    (net (code "37") (name "Net-(Q1-G)") (class "Default")
      (node (ref "Q1") (pin "1") (pinfunction "G_1") (pintype "unspecified"))
      (node (ref "R50") (pin "2") (pinfunction "2_2") (pintype "input"))
      (node (ref "R51") (pin "2") (pinfunction "2_2") (pintype "input"))
    )
    (net (code "38") (name "Net-(Q2-D)") (class "Default")
      (node (ref "C33") (pin "1") (pinfunction "1_1") (pintype "input"))
      (node (ref "Q2") (pin "3") (pinfunction "D_3") (pintype "unspecified"))
      (node (ref "U97") (pin "1") (pinfunction "1_1") (pintype "input"))
    )
    (net (code "39") (name "Net-(Q2-G)") (class "Default")
      (node (ref "Q2") (pin "1") (pinfunction "G_1") (pintype "unspecified"))
      (node (ref "R52") (pin "2") (pinfunction "2_2") (pintype "input"))
      (node (ref "R53") (pin "2") (pinfunction "2_2") (pintype "input"))
    )
    (net (code "40") (name "Net-(Q3-D)") (class "Default")
      (node (ref "C34") (pin "1") (pinfunction "1_1") (pintype "input"))
      (node (ref "Q3") (pin "3") (pinfunction "D_3") (pintype "unspecified"))
      (node (ref "U91") (pin "1") (pinfunction "1_1") (pintype "input"))
    )
    (net (code "41") (name "Net-(Q3-G)") (class "Default")
      (node (ref "Q3") (pin "1") (pinfunction "G_1") (pintype "unspecified"))
      (node (ref "R54") (pin "2") (pinfunction "2_2") (pintype "input"))
      (node (ref "R55") (pin "2") (pinfunction "2_2") (pintype "input"))
    )
    (net (code "42") (name "Net-(Q4-D)") (class "Default")
      (node (ref "C35") (pin "1") (pinfunction "1_1") (pintype "input"))
      (node (ref "Q4") (pin "3") (pinfunction "D_3") (pintype "unspecified"))
      (node (ref "U93") (pin "1") (pinfunction "1_1") (pintype "input"))
    )
    (net (code "43") (name "Net-(Q4-G)") (class "Default")
      (node (ref "Q4") (pin "1") (pinfunction "G_1") (pintype "unspecified"))
      (node (ref "R56") (pin "2") (pinfunction "2_2") (pintype "input"))
      (node (ref "R57") (pin "2") (pinfunction "2_2") (pintype "input"))
    )
    (net (code "44") (name "Net-(U43-PROG)") (class "Default")
      (node (ref "R4") (pin "2") (pinfunction "2_2") (pintype "input"))
      (node (ref "U43") (pin "2") (pinfunction "PROG_2") (pintype "unspecified"))
    )
    (net (code "45") (name "Net-(U89-CC1)") (class "Default")
      (node (ref "R46") (pin "2") (pinfunction "2_2") (pintype "input"))
      (node (ref "U89") (pin "A5") (pinfunction "CC1_A5") (pintype "unspecified"))
    )
    (net (code "46") (name "Net-(U89-CC2)") (class "Default")
      (node (ref "R47") (pin "1") (pinfunction "1_1") (pintype "input"))
      (node (ref "U89") (pin "B5") (pinfunction "CC2_B5") (pintype "unspecified"))
    )
    (net (code "47") (name "unconnected-(U14-PB0-Pad17)") (class "Default")
      (node (ref "U14") (pin "17") (pinfunction "PB0_17") (pintype "unspecified+no_connect"))
    )
    (net (code "48") (name "unconnected-(U14-PB1-Pad18)") (class "Default")
      (node (ref "U14") (pin "18") (pinfunction "PB1_18") (pintype "unspecified+no_connect"))
    )
    (net (code "49") (name "unconnected-(U14-PB2-Pad19)") (class "Default")
      (node (ref "U14") (pin "19") (pinfunction "PB2_19") (pintype "unspecified+no_connect"))
    )
    (net (code "50") (name "unconnected-(U14-PB4-Pad42)") (class "Default")
      (node (ref "U14") (pin "42") (pinfunction "PB4_42") (pintype "unspecified+no_connect"))
    )
    (net (code "51") (name "unconnected-(U14-PB5-Pad43)") (class "Default")
      (node (ref "U14") (pin "43") (pinfunction "PB5_43") (pintype "unspecified+no_connect"))
    )
    (net (code "52") (name "unconnected-(U14-PB6-Pad44)") (class "Default")
      (node (ref "U14") (pin "44") (pinfunction "PB6_44") (pintype "unspecified+no_connect"))
    )
    (net (code "53") (name "unconnected-(U14-PB7-Pad45)") (class "Default")
      (node (ref "U14") (pin "45") (pinfunction "PB7_45") (pintype "unspecified+no_connect"))
    )
    (net (code "54") (name "unconnected-(U14-PB9-Pad47)") (class "Default")
      (node (ref "U14") (pin "47") (pinfunction "PB9_47") (pintype "unspecified+no_connect"))
    )
    (net (code "55") (name "unconnected-(U14-PB12-Pad25)") (class "Default")
      (node (ref "U14") (pin "25") (pinfunction "PB12_25") (pintype "unspecified+no_connect"))
    )
    (net (code "56") (name "unconnected-(U14-PB13-Pad26)") (class "Default")
      (node (ref "U14") (pin "26") (pinfunction "PB13_26") (pintype "unspecified+no_connect"))
    )
    (net (code "57") (name "unconnected-(U14-PB14-Pad27)") (class "Default")
      (node (ref "U14") (pin "27") (pinfunction "PB14_27") (pintype "unspecified+no_connect"))
    )
    (net (code "58") (name "unconnected-(U14-PB15-Pad28)") (class "Default")
      (node (ref "U14") (pin "28") (pinfunction "PB15_28") (pintype "unspecified+no_connect"))
    )
    (net (code "59") (name "unconnected-(U14-PC6-Pad29)") (class "Default")
      (node (ref "U14") (pin "29") (pinfunction "PC6_29") (pintype "unspecified+no_connect"))
    )
    (net (code "60") (name "unconnected-(U14-PC10-Pad39)") (class "Default")
      (node (ref "U14") (pin "39") (pinfunction "PC10_39") (pintype "unspecified+no_connect"))
    )
    (net (code "61") (name "unconnected-(U14-PC11-Pad40)") (class "Default")
      (node (ref "U14") (pin "40") (pinfunction "PC11_40") (pintype "unspecified+no_connect"))
    )
    (net (code "62") (name "unconnected-(U14-PC13-Pad2)") (class "Default")
      (node (ref "U14") (pin "2") (pinfunction "PC13_2") (pintype "unspecified+no_connect"))
    )
    (net (code "63") (name "unconnected-(U14-PC14-OSC32_IN-Pad3)") (class "Default")
      (node (ref "U14") (pin "3") (pinfunction "PC14-OSC32_IN_3") (pintype "unspecified+no_connect"))
    )
    (net (code "64") (name "unconnected-(U14-PC15-OSC32_OUT-Pad4)") (class "Default")
      (node (ref "U14") (pin "4") (pinfunction "PC15-OSC32_OUT_4") (pintype "unspecified+no_connect"))
    )
    (net (code "65") (name "unconnected-(U33-INT1-Pad4)") (class "Default")
      (node (ref "U33") (pin "4") (pinfunction "INT1_4") (pintype "unspecified+no_connect"))
    )
    (net (code "66") (name "unconnected-(U33-INT2-Pad9)") (class "Default")
      (node (ref "U33") (pin "9") (pinfunction "INT2_9") (pintype "unspecified+no_connect"))
    )
    (net (code "67") (name "unconnected-(U33-NC-Pad10)") (class "Default")
      (node (ref "U33") (pin "10") (pinfunction "NC_10") (pintype "unspecified+no_connect"))
    )
    (net (code "68") (name "unconnected-(U33-NC-Pad11)") (class "Default")
      (node (ref "U33") (pin "11") (pinfunction "NC_11") (pintype "unspecified+no_connect"))
    )
    (net (code "69") (name "unconnected-(U39-Pad5)") (class "Default")
      (node (ref "U39") (pin "5") (pinfunction "5_5") (pintype "unspecified+no_connect"))
    )
    (net (code "70") (name "unconnected-(U39-Pad6)") (class "Default")
      (node (ref "U39") (pin "6") (pinfunction "6_6") (pintype "unspecified+no_connect"))
    )
    (net (code "71") (name "unconnected-(U41-Pad5)") (class "Default")
      (node (ref "U41") (pin "5") (pinfunction "5_5") (pintype "unspecified+no_connect"))
    )
    (net (code "72") (name "unconnected-(U41-Pad6)") (class "Default")
      (node (ref "U41") (pin "6") (pinfunction "6_6") (pintype "unspecified+no_connect"))
    )
    (net (code "73") (name "unconnected-(U89-SBU1-PadA8)") (class "Default")
      (node (ref "U89") (pin "A8") (pinfunction "SBU1_A8") (pintype "unspecified+no_connect"))
    )
    (net (code "74") (name "unconnected-(U89-SBU2-PadB8)") (class "Default")
      (node (ref "U89") (pin "B8") (pinfunction "SBU2_B8") (pintype "unspecified+no_connect"))
    )
    (net (code "75") (name "unconnected-(U98-Pad5)") (class "Default")
      (node (ref "U98") (pin "5") (pinfunction "5_5") (pintype "unspecified+no_connect"))
    )
    (net (code "76") (name "unconnected-(U98-Pad6)") (class "Default")
      (node (ref "U98") (pin "6") (pinfunction "6_6") (pintype "unspecified+no_connect"))
    )
  )
)
